# ledring.net
KiCad netlist of a schematic drawn in Altium Designer
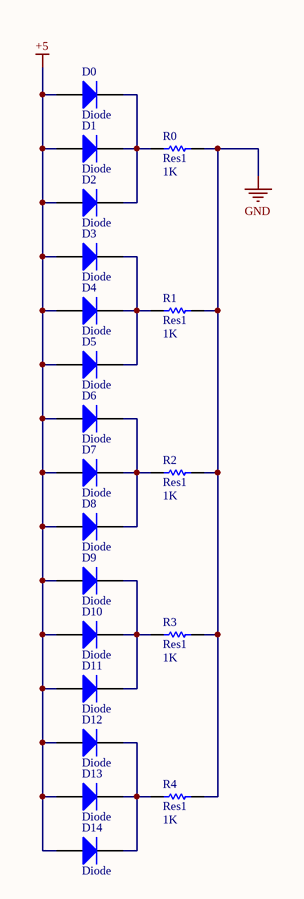
[diagram p0: ledring.SchDoc]

(export (version "E")
  (design (tool "Eeschema 10.0.6"))
  (components
    (comp (ref "D0")
      (value "Diode")
      (footprint "SMC")
      (description "Default Diode")
      (fields (field (name "PUBLISHER") "Altium Limited"))
      (libsource (lib "Miscellaneous Devices") (part "Diode"))
    )
    (comp (ref "D1")
      (value "Diode")
      (footprint "SMC")
      (description "Default Diode")
      (fields (field (name "PUBLISHER") "Altium Limited"))
      (libsource (lib "Miscellaneous Devices") (part "Diode"))
    )
    (comp (ref "D2")
      (value "Diode")
      (footprint "SMC")
      (description "Default Diode")
      (fields (field (name "PUBLISHER") "Altium Limited"))
      (libsource (lib "Miscellaneous Devices") (part "Diode"))
    )
    (comp (ref "D3")
      (value "Diode")
      (footprint "SMC")
      (description "Default Diode")
      (fields (field (name "PUBLISHER") "Altium Limited"))
      (libsource (lib "Miscellaneous Devices") (part "Diode"))
    )
    (comp (ref "D4")
      (value "Diode")
      (footprint "SMC")
      (description "Default Diode")
      (fields (field (name "PUBLISHER") "Altium Limited"))
      (libsource (lib "Miscellaneous Devices") (part "Diode"))
    )
    (comp (ref "D5")
      (value "Diode")
      (footprint "SMC")
      (description "Default Diode")
      (fields (field (name "PUBLISHER") "Altium Limited"))
      (libsource (lib "Miscellaneous Devices") (part "Diode"))
    )
    (comp (ref "D6")
      (value "Diode")
      (footprint "SMC")
      (description "Default Diode")
      (fields (field (name "PUBLISHER") "Altium Limited"))
      (libsource (lib "Miscellaneous Devices") (part "Diode"))
    )
    (comp (ref "D7")
      (value "Diode")
      (footprint "SMC")
      (description "Default Diode")
      (fields (field (name "PUBLISHER") "Altium Limited"))
      (libsource (lib "Miscellaneous Devices") (part "Diode"))
    )
    (comp (ref "D8")
      (value "Diode")
      (footprint "SMC")
      (description "Default Diode")
      (fields (field (name "PUBLISHER") "Altium Limited"))
      (libsource (lib "Miscellaneous Devices") (part "Diode"))
    )
    (comp (ref "D9")
      (value "Diode")
      (footprint "SMC")
      (description "Default Diode")
      (fields (field (name "PUBLISHER") "Altium Limited"))
      (libsource (lib "Miscellaneous Devices") (part "Diode"))
    )
    (comp (ref "D10")
      (value "Diode")
      (footprint "SMC")
      (description "Default Diode")
      (fields (field (name "PUBLISHER") "Altium Limited"))
      (libsource (lib "Miscellaneous Devices") (part "Diode"))
    )
    (comp (ref "D11")
      (value "Diode")
      (footprint "SMC")
      (description "Default Diode")
      (fields (field (name "PUBLISHER") "Altium Limited"))
      (libsource (lib "Miscellaneous Devices") (part "Diode"))
    )
    (comp (ref "D12")
      (value "Diode")
      (footprint "SMC")
      (description "Default Diode")
      (fields (field (name "PUBLISHER") "Altium Limited"))
      (libsource (lib "Miscellaneous Devices") (part "Diode"))
    )
    (comp (ref "D13")
      (value "Diode")
      (footprint "SMC")
      (description "Default Diode")
      (fields (field (name "PUBLISHER") "Altium Limited"))
      (libsource (lib "Miscellaneous Devices") (part "Diode"))
    )
    (comp (ref "D14")
      (value "Diode")
      (footprint "SMC")
      (description "Default Diode")
      (fields (field (name "PUBLISHER") "Altium Limited"))
      (libsource (lib "Miscellaneous Devices") (part "Diode"))
    )
    (comp (ref "R0")
      (value "Res1")
      (footprint "AXIAL-0.3")
      (description "Resistor")
      (fields (field (name "ALTIUM_VALUE") "1K") (field (name "PUBLISHER") "Altium Limited"))
      (libsource (lib "Miscellaneous Devices") (part "Res1"))
    )
    (comp (ref "R1")
      (value "Res1")
      (footprint "AXIAL-0.3")
      (description "Resistor")
      (fields (field (name "ALTIUM_VALUE") "1K") (field (name "PUBLISHER") "Altium Limited"))
      (libsource (lib "Miscellaneous Devices") (part "Res1"))
    )
    (comp (ref "R2")
      (value "Res1")
      (footprint "AXIAL-0.3")
      (description "Resistor")
      (fields (field (name "ALTIUM_VALUE") "1K") (field (name "PUBLISHER") "Altium Limited"))
      (libsource (lib "Miscellaneous Devices") (part "Res1"))
    )
    (comp (ref "R3")
      (value "Res1")
      (footprint "AXIAL-0.3")
      (description "Resistor")
      (fields (field (name "ALTIUM_VALUE") "1K") (field (name "PUBLISHER") "Altium Limited"))
      (libsource (lib "Miscellaneous Devices") (part "Res1"))
    )
    (comp (ref "R4")
      (value "Res1")
      (footprint "AXIAL-0.3")
      (description "Resistor")
      (fields (field (name "ALTIUM_VALUE") "1K") (field (name "PUBLISHER") "Altium Limited"))
      (libsource (lib "Miscellaneous Devices") (part "Res1"))
    )
  )
  (nets
    (net (code "1") (name "+5") (class "Default")
      (node (ref "D0") (pin "1") (pinfunction "A_1") (pintype "passive"))
      (node (ref "D1") (pin "1") (pinfunction "A_1") (pintype "passive"))
      (node (ref "D10") (pin "1") (pinfunction "A_1") (pintype "passive"))
      (node (ref "D11") (pin "1") (pinfunction "A_1") (pintype "passive"))
      (node (ref "D12") (pin "1") (pinfunction "A_1") (pintype "passive"))
      (node (ref "D13") (pin "1") (pinfunction "A_1") (pintype "passive"))
      (node (ref "D14") (pin "1") (pinfunction "A_1") (pintype "passive"))
      (node (ref "D2") (pin "1") (pinfunction "A_1") (pintype "passive"))
      (node (ref "D3") (pin "1") (pinfunction "A_1") (pintype "passive"))
      (node (ref "D4") (pin "1") (pinfunction "A_1") (pintype "passive"))
      (node (ref "D5") (pin "1") (pinfunction "A_1") (pintype "passive"))
      (node (ref "D6") (pin "1") (pinfunction "A_1") (pintype "passive"))
      (node (ref "D7") (pin "1") (pinfunction "A_1") (pintype "passive"))
      (node (ref "D8") (pin "1") (pinfunction "A_1") (pintype "passive"))
      (node (ref "D9") (pin "1") (pinfunction "A_1") (pintype "passive"))
    )
    (net (code "2") (name "GND") (class "Default")
      (node (ref "R0") (pin "2") (pinfunction "2_2") (pintype "passive"))
      (node (ref "R1") (pin "2") (pinfunction "2_2") (pintype "passive"))
      (node (ref "R2") (pin "2") (pinfunction "2_2") (pintype "passive"))
      (node (ref "R3") (pin "2") (pinfunction "2_2") (pintype "passive"))
      (node (ref "R4") (pin "2") (pinfunction "2_2") (pintype "passive"))
    )
    (net (code "3") (name "Net-(D0-K)") (class "Default")
      (node (ref "D0") (pin "2") (pinfunction "K_2") (pintype "passive"))
      (node (ref "D1") (pin "2") (pinfunction "K_2") (pintype "passive"))
      (node (ref "D2") (pin "2") (pinfunction "K_2") (pintype "passive"))
      (node (ref "R0") (pin "1") (pinfunction "1_1") (pintype "passive"))
    )
    (net (code "4") (name "Net-(D3-K)") (class "Default")
      (node (ref "D3") (pin "2") (pinfunction "K_2") (pintype "passive"))
      (node (ref "D4") (pin "2") (pinfunction "K_2") (pintype "passive"))
      (node (ref "D5") (pin "2") (pinfunction "K_2") (pintype "passive"))
      (node (ref "R1") (pin "1") (pinfunction "1_1") (pintype "passive"))
    )
    (net (code "5") (name "Net-(D6-K)") (class "Default")
      (node (ref "D6") (pin "2") (pinfunction "K_2") (pintype "passive"))
      (node (ref "D7") (pin "2") (pinfunction "K_2") (pintype "passive"))
      (node (ref "D8") (pin "2") (pinfunction "K_2") (pintype "passive"))
      (node (ref "R2") (pin "1") (pinfunction "1_1") (pintype "passive"))
    )
    (net (code "6") (name "Net-(D10-K)") (class "Default")
      (node (ref "D10") (pin "2") (pinfunction "K_2") (pintype "passive"))
      (node (ref "D11") (pin "2") (pinfunction "K_2") (pintype "passive"))
      (node (ref "D9") (pin "2") (pinfunction "K_2") (pintype "passive"))
      (node (ref "R3") (pin "1") (pinfunction "1_1") (pintype "passive"))
    )
    (net (code "7") (name "Net-(D12-K)") (class "Default")
      (node (ref "D12") (pin "2") (pinfunction "K_2") (pintype "passive"))
      (node (ref "D13") (pin "2") (pinfunction "K_2") (pintype "passive"))
      (node (ref "D14") (pin "2") (pinfunction "K_2") (pintype "passive"))
      (node (ref "R4") (pin "1") (pinfunction "1_1") (pintype "passive"))
    )
  )
)
